# Flight_Computer.net
KiCad netlist of a schematic drawn in EAGLE
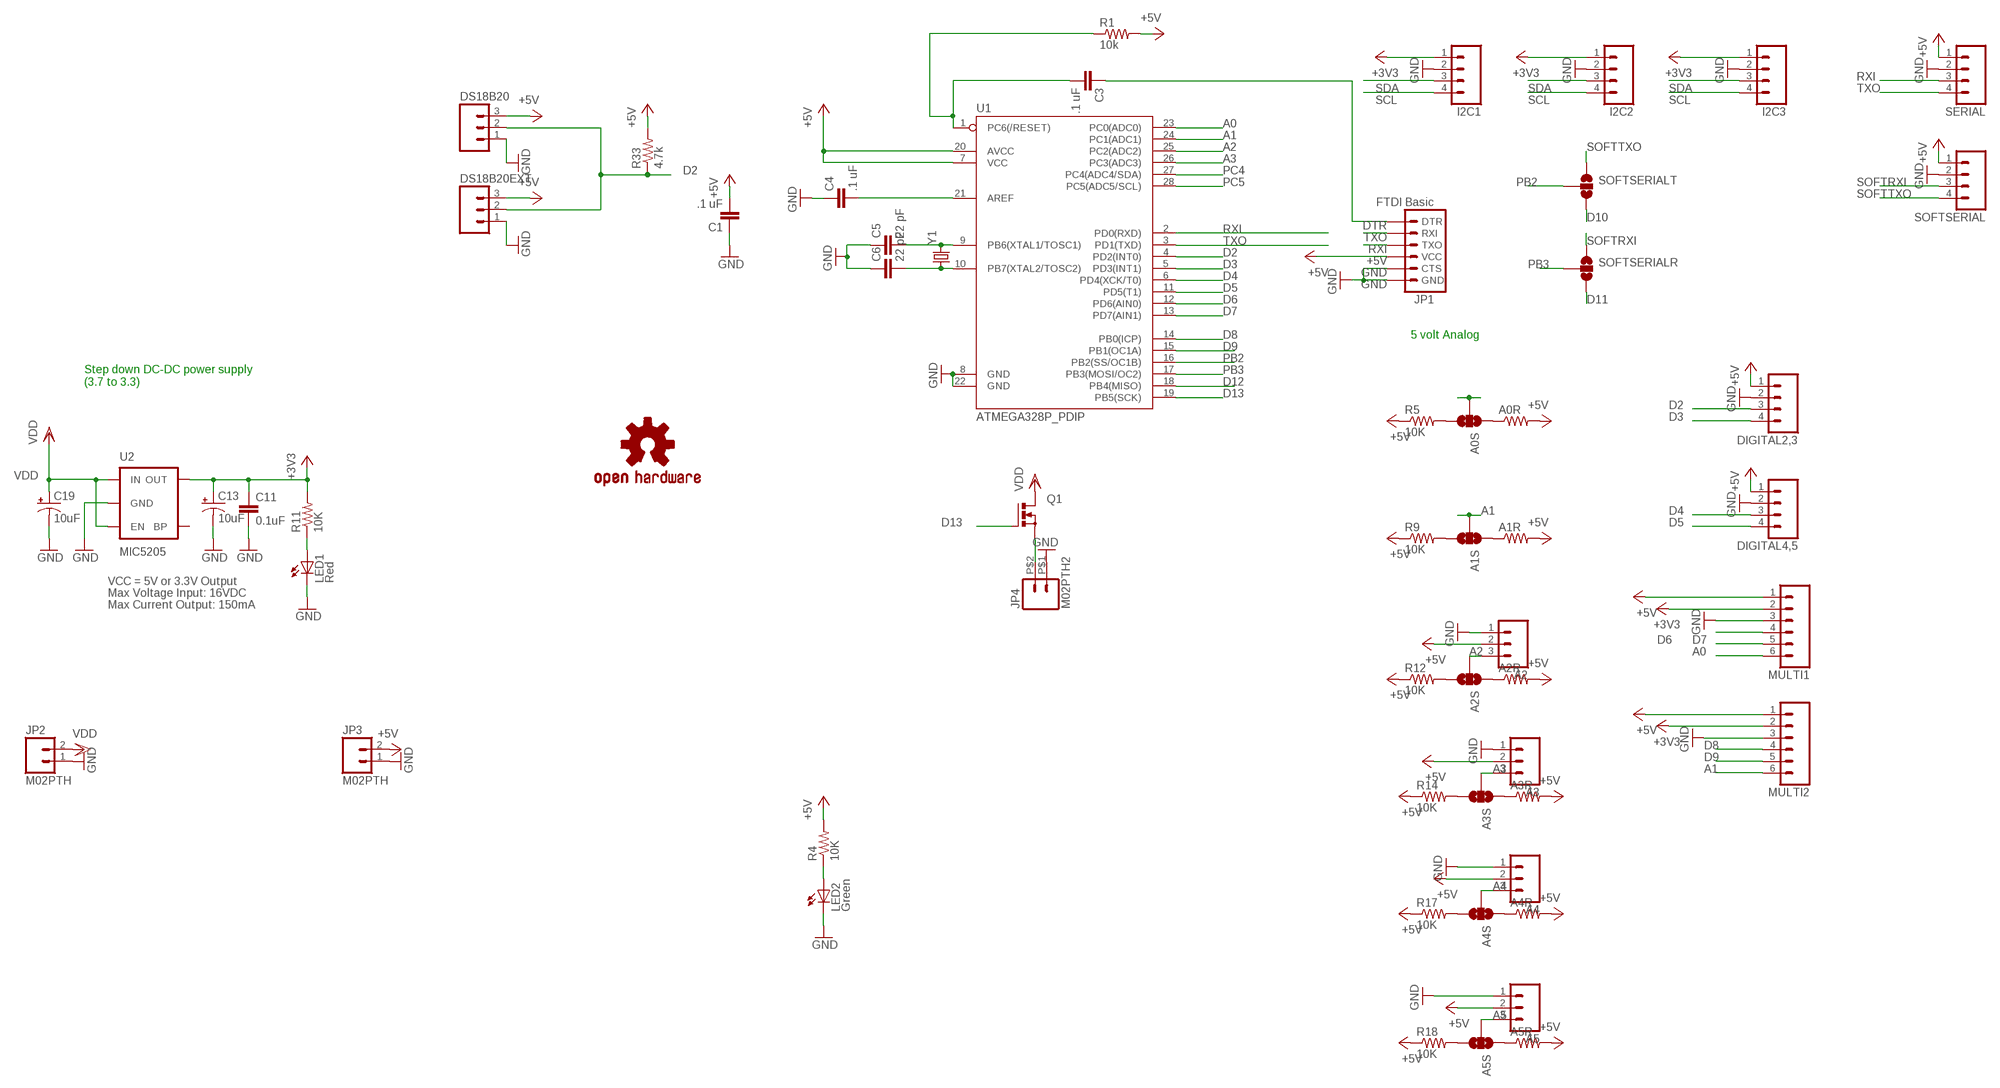
[diagram p0: schematic, sheet 1]

(export (version "E")
  (design (tool "Eeschema 10.0.6"))
  (components
    (comp (ref "A0R")
      (value "RESISTORAXIAL-0.3")
      (footprint "eagle-import:AXIAL-0.3")
      (libsource (lib "eagle-import") (part "SparkFun-Passives_RESISTORAXIAL-0.3"))
    )
    (comp (ref "A0S")
      (value "SOLDERJUMPER_2WAYPASTE2&3")
      (footprint "eagle-import:SJ_3_PASTE2&3")
      (libsource (lib "eagle-import") (part "SOLDERJUMPER_2WAYPASTE2&3"))
    )
    (comp (ref "A1R")
      (value "RESISTORAXIAL-0.3")
      (footprint "eagle-import:AXIAL-0.3")
      (libsource (lib "eagle-import") (part "SparkFun-Passives_RESISTORAXIAL-0.3"))
    )
    (comp (ref "A1S")
      (value "SOLDERJUMPER_2WAYPASTE2&3")
      (footprint "eagle-import:SJ_3_PASTE2&3")
      (libsource (lib "eagle-import") (part "SOLDERJUMPER_2WAYPASTE2&3"))
    )
    (comp (ref "A2")
      (value "M03POLAR")
      (footprint "eagle-import:MOLEX-1X3")
      (libsource (lib "eagle-import") (part "M03POLAR"))
    )
    (comp (ref "A2R")
      (value "RESISTORAXIAL-0.3")
      (footprint "eagle-import:AXIAL-0.3")
      (libsource (lib "eagle-import") (part "SparkFun-Passives_RESISTORAXIAL-0.3"))
    )
    (comp (ref "A2S")
      (value "SOLDERJUMPER_2WAYPASTE2&3")
      (footprint "eagle-import:SJ_3_PASTE2&3")
      (libsource (lib "eagle-import") (part "SOLDERJUMPER_2WAYPASTE2&3"))
    )
    (comp (ref "A3")
      (value "M03POLAR")
      (footprint "eagle-import:MOLEX-1X3")
      (libsource (lib "eagle-import") (part "M03POLAR"))
    )
    (comp (ref "A3R")
      (value "RESISTORAXIAL-0.3")
      (footprint "eagle-import:AXIAL-0.3")
      (libsource (lib "eagle-import") (part "SparkFun-Passives_RESISTORAXIAL-0.3"))
    )
    (comp (ref "A3S")
      (value "SOLDERJUMPER_2WAYPASTE2&3")
      (footprint "eagle-import:SJ_3_PASTE2&3")
      (libsource (lib "eagle-import") (part "SOLDERJUMPER_2WAYPASTE2&3"))
    )
    (comp (ref "A4")
      (value "M03POLAR")
      (footprint "eagle-import:MOLEX-1X3")
      (libsource (lib "eagle-import") (part "M03POLAR"))
    )
    (comp (ref "A4R")
      (value "RESISTORAXIAL-0.3")
      (footprint "eagle-import:AXIAL-0.3")
      (libsource (lib "eagle-import") (part "SparkFun-Passives_RESISTORAXIAL-0.3"))
    )
    (comp (ref "A4S")
      (value "SOLDERJUMPER_2WAYPASTE2&3")
      (footprint "eagle-import:SJ_3_PASTE2&3")
      (libsource (lib "eagle-import") (part "SOLDERJUMPER_2WAYPASTE2&3"))
    )
    (comp (ref "A5")
      (value "M03POLAR")
      (footprint "eagle-import:MOLEX-1X3")
      (libsource (lib "eagle-import") (part "M03POLAR"))
    )
    (comp (ref "A5R")
      (value "RESISTORAXIAL-0.3")
      (footprint "eagle-import:AXIAL-0.3")
      (libsource (lib "eagle-import") (part "SparkFun-Passives_RESISTORAXIAL-0.3"))
    )
    (comp (ref "A5S")
      (value "SOLDERJUMPER_2WAYPASTE2&3")
      (footprint "eagle-import:SJ_3_PASTE2&3")
      (libsource (lib "eagle-import") (part "SOLDERJUMPER_2WAYPASTE2&3"))
    )
    (comp (ref "C1")
      (value ".1 uF")
      (footprint "eagle-import:1206")
      (libsource (lib "eagle-import") (part "SparkFun-Passives_CAP1206"))
    )
    (comp (ref "C3")
      (value ".1 uF")
      (footprint "eagle-import:1206")
      (libsource (lib "eagle-import") (part "SparkFun-Passives_CAP1206"))
    )
    (comp (ref "C4")
      (value ".1 uF")
      (footprint "eagle-import:1206")
      (libsource (lib "eagle-import") (part "SparkFun-Passives_CAP1206"))
    )
    (comp (ref "C5")
      (value "22 pF")
      (footprint "eagle-import:CAP-PTH-5MM")
      (libsource (lib "eagle-import") (part "SparkFun-Passives_CAPPTH1"))
    )
    (comp (ref "C6")
      (value "22 pF")
      (footprint "eagle-import:CAP-PTH-5MM")
      (libsource (lib "eagle-import") (part "SparkFun-Passives_CAPPTH1"))
    )
    (comp (ref "C11")
      (value "0.1uF")
      (footprint "eagle-import:1206")
      (libsource (lib "eagle-import") (part "CAP1206"))
    )
    (comp (ref "C13")
      (value "10uF")
      (footprint "eagle-import:EIA3216")
      (libsource (lib "eagle-import") (part "CAP_POL1206"))
    )
    (comp (ref "C19")
      (value "10uF")
      (footprint "eagle-import:EIA3216")
      (libsource (lib "eagle-import") (part "CAP_POL1206"))
    )
    (comp (ref "DIGITAL2,3")
      (value "M04POLAR")
      (footprint "eagle-import:MOLEX-1X4")
      (libsource (lib "eagle-import") (part "M04POLAR"))
    )
    (comp (ref "DIGITAL4,5")
      (value "M04POLAR")
      (footprint "eagle-import:MOLEX-1X4")
      (libsource (lib "eagle-import") (part "M04POLAR"))
    )
    (comp (ref "DS18B20")
      (value "M03PTH")
      (footprint "eagle-import:1X03")
      (libsource (lib "eagle-import") (part "M03PTH"))
    )
    (comp (ref "DS18B20EXT")
      (value "M03POLAR")
      (footprint "eagle-import:MOLEX-1X3")
      (libsource (lib "eagle-import") (part "M03POLAR"))
    )
    (comp (ref "I2C1")
      (value "M04POLAR")
      (footprint "eagle-import:MOLEX-1X4")
      (libsource (lib "eagle-import") (part "M04POLAR"))
    )
    (comp (ref "I2C2")
      (value "M04POLAR")
      (footprint "eagle-import:MOLEX-1X4")
      (libsource (lib "eagle-import") (part "M04POLAR"))
    )
    (comp (ref "I2C3")
      (value "M04POLAR")
      (footprint "eagle-import:MOLEX-1X4")
      (libsource (lib "eagle-import") (part "M04POLAR"))
    )
    (comp (ref "JP1")
      (value "FTDI Basic")
      (footprint "eagle-import:1X06")
      (libsource (lib "eagle-import") (part "ARDUINO_SERIAL_PROGRAMPTH"))
    )
    (comp (ref "JP2")
      (value "M02PTH")
      (footprint "eagle-import:1X02")
      (libsource (lib "eagle-import") (part "M02PTH"))
    )
    (comp (ref "JP3")
      (value "M02PTH")
      (footprint "eagle-import:1X02")
      (libsource (lib "eagle-import") (part "M02PTH"))
    )
    (comp (ref "JP4")
      (value "M02PTH2")
      (footprint "eagle-import:1X02_BIG")
      (libsource (lib "eagle-import") (part "M02PTH2"))
    )
    (comp (ref "LED1")
      (value "Red")
      (footprint "eagle-import:LED-0603")
      (libsource (lib "eagle-import") (part "LED0603"))
    )
    (comp (ref "LED2")
      (value "Green")
      (footprint "eagle-import:LED-0603")
      (libsource (lib "eagle-import") (part "LED0603"))
    )
    (comp (ref "LOGO1")
      (value "OSHW-LOGOL")
      (footprint "eagle-import:OSHW-LOGO-L")
      (libsource (lib "eagle-import") (part "OSHW-LOGOL"))
    )
    (comp (ref "MULTI1")
      (value "M06POLAR")
      (footprint "eagle-import:MOLEX-1X6")
      (libsource (lib "eagle-import") (part "M06POLAR"))
    )
    (comp (ref "MULTI2")
      (value "M06POLAR")
      (footprint "eagle-import:MOLEX-1X6")
      (libsource (lib "eagle-import") (part "M06POLAR"))
    )
    (comp (ref "Q1")
      (value "PMOSFET_NTO220BV")
      (footprint "eagle-import:TO220BV")
      (libsource (lib "eagle-import") (part "PMOSFET_NTO220BV"))
    )
    (comp (ref "R1")
      (value "10k")
      (footprint "eagle-import:1206")
      (libsource (lib "eagle-import") (part "SparkFun-Passives_RESISTOR1206"))
    )
    (comp (ref "R4")
      (value "10K")
      (footprint "eagle-import:1206")
      (libsource (lib "eagle-import") (part "RESISTOR1206"))
    )
    (comp (ref "R5")
      (value "10K")
      (footprint "eagle-import:1206")
      (libsource (lib "eagle-import") (part "SparkFun-Passives_RESISTOR1206"))
    )
    (comp (ref "R9")
      (value "10K")
      (footprint "eagle-import:1206")
      (libsource (lib "eagle-import") (part "SparkFun-Passives_RESISTOR1206"))
    )
    (comp (ref "R11")
      (value "10K")
      (footprint "eagle-import:1206")
      (libsource (lib "eagle-import") (part "RESISTOR1206"))
    )
    (comp (ref "R12")
      (value "10K")
      (footprint "eagle-import:1206")
      (libsource (lib "eagle-import") (part "SparkFun-Passives_RESISTOR1206"))
    )
    (comp (ref "R14")
      (value "10K")
      (footprint "eagle-import:1206")
      (libsource (lib "eagle-import") (part "SparkFun-Passives_RESISTOR1206"))
    )
    (comp (ref "R17")
      (value "10K")
      (footprint "eagle-import:1206")
      (libsource (lib "eagle-import") (part "SparkFun-Passives_RESISTOR1206"))
    )
    (comp (ref "R18")
      (value "10K")
      (footprint "eagle-import:1206")
      (libsource (lib "eagle-import") (part "SparkFun-Passives_RESISTOR1206"))
    )
    (comp (ref "R33")
      (value "4.7k")
      (footprint "eagle-import:1206")
      (libsource (lib "eagle-import") (part "SparkFun-Passives_RESISTOR1206"))
    )
    (comp (ref "SERIAL")
      (value "M04POLAR")
      (footprint "eagle-import:MOLEX-1X4")
      (libsource (lib "eagle-import") (part "M04POLAR"))
    )
    (comp (ref "SOFTSERIAL")
      (value "M04POLAR")
      (footprint "eagle-import:MOLEX-1X4")
      (libsource (lib "eagle-import") (part "M04POLAR"))
    )
    (comp (ref "SOFTSERIALR")
      (value "SOLDERJUMPER_2WAYPASTE2&3")
      (footprint "eagle-import:SJ_3_PASTE2&3")
      (libsource (lib "eagle-import") (part "SOLDERJUMPER_2WAYPASTE2&3"))
    )
    (comp (ref "SOFTSERIALT")
      (value "SOLDERJUMPER_2WAYPASTE2&3")
      (footprint "eagle-import:SJ_3_PASTE2&3")
      (libsource (lib "eagle-import") (part "SOLDERJUMPER_2WAYPASTE2&3"))
    )
    (comp (ref "U1")
      (value "ATMEGA328P_PDIP")
      (footprint "eagle-import:DIL28-3")
      (libsource (lib "eagle-import") (part "ATMEGA328P_PDIP"))
    )
    (comp (ref "U2")
      (value "MIC5205")
      (footprint "eagle-import:SOT23-5")
      (libsource (lib "eagle-import") (part "V_REG_LDOSMD"))
    )
    (comp (ref "Y1")
      (value "CRYSTALHC49UV")
      (footprint "eagle-import:HC49U-V")
      (libsource (lib "eagle-import") (part "CRYSTALHC49UV"))
    )
  )
  (nets
    (net (code "1") (name "+3V3") (class "Default")
      (node (ref "C11") (pin "1") (pinfunction "1_1") (pintype "passive"))
      (node (ref "C13") (pin "A") (pinfunction "+_A") (pintype "passive"))
      (node (ref "I2C1") (pin "1") (pinfunction "1_1") (pintype "passive"))
      (node (ref "I2C2") (pin "1") (pinfunction "1_1") (pintype "passive"))
      (node (ref "I2C3") (pin "1") (pinfunction "1_1") (pintype "passive"))
      (node (ref "MULTI1") (pin "2") (pinfunction "2_2") (pintype "passive"))
      (node (ref "MULTI2") (pin "2") (pinfunction "2_2") (pintype "passive"))
      (node (ref "R11") (pin "2") (pinfunction "2_2") (pintype "passive"))
      (node (ref "U2") (pin "5") (pinfunction "OUT_5") (pintype "passive"))
    )
    (net (code "2") (name "+5V") (class "Default")
      (node (ref "A0R") (pin "P$2") (pinfunction "2_P$2") (pintype "passive"))
      (node (ref "A1R") (pin "P$2") (pinfunction "2_P$2") (pintype "passive"))
      (node (ref "A2") (pin "2") (pinfunction "2_2") (pintype "passive"))
      (node (ref "A2R") (pin "P$2") (pinfunction "2_P$2") (pintype "passive"))
      (node (ref "A3") (pin "2") (pinfunction "2_2") (pintype "passive"))
      (node (ref "A3R") (pin "P$2") (pinfunction "2_P$2") (pintype "passive"))
      (node (ref "A4") (pin "2") (pinfunction "2_2") (pintype "passive"))
      (node (ref "A4R") (pin "P$2") (pinfunction "2_P$2") (pintype "passive"))
      (node (ref "A5") (pin "2") (pinfunction "2_2") (pintype "passive"))
      (node (ref "A5R") (pin "P$2") (pinfunction "2_P$2") (pintype "passive"))
      (node (ref "C1") (pin "2") (pinfunction "2_2") (pintype "passive"))
      (node (ref "DIGITAL2,3") (pin "1") (pinfunction "1_1") (pintype "passive"))
      (node (ref "DIGITAL4,5") (pin "1") (pinfunction "1_1") (pintype "passive"))
      (node (ref "DS18B20") (pin "3") (pinfunction "3_3") (pintype "passive"))
      (node (ref "DS18B20EXT") (pin "3") (pinfunction "3_3") (pintype "passive"))
      (node (ref "JP1") (pin "4") (pinfunction "VCC_4") (pintype "passive"))
      (node (ref "JP3") (pin "2") (pinfunction "2_2") (pintype "passive"))
      (node (ref "MULTI1") (pin "1") (pinfunction "1_1") (pintype "passive"))
      (node (ref "MULTI2") (pin "1") (pinfunction "1_1") (pintype "passive"))
      (node (ref "R1") (pin "2") (pinfunction "2_2") (pintype "passive"))
      (node (ref "R12") (pin "1") (pinfunction "1_1") (pintype "passive"))
      (node (ref "R14") (pin "1") (pinfunction "1_1") (pintype "passive"))
      (node (ref "R17") (pin "1") (pinfunction "1_1") (pintype "passive"))
      (node (ref "R18") (pin "1") (pinfunction "1_1") (pintype "passive"))
      (node (ref "R33") (pin "2") (pinfunction "2_2") (pintype "passive"))
      (node (ref "R4") (pin "2") (pinfunction "2_2") (pintype "passive"))
      (node (ref "R5") (pin "1") (pinfunction "1_1") (pintype "passive"))
      (node (ref "R9") (pin "1") (pinfunction "1_1") (pintype "passive"))
      (node (ref "SERIAL") (pin "1") (pinfunction "1_1") (pintype "passive"))
      (node (ref "SOFTSERIAL") (pin "1") (pinfunction "1_1") (pintype "passive"))
      (node (ref "U1") (pin "20") (pinfunction "AVCC_20") (pintype "bidirectional"))
      (node (ref "U1") (pin "7") (pinfunction "VCC_7") (pintype "bidirectional"))
    )
    (net (code "3") (name "/A0") (class "Default")
      (node (ref "A0S") (pin "2") (pinfunction "2_2") (pintype "passive"))
      (node (ref "MULTI1") (pin "6") (pinfunction "6_6") (pintype "passive"))
      (node (ref "U1") (pin "23") (pinfunction "PC0(ADC0)_23") (pintype "bidirectional"))
    )
    (net (code "4") (name "/A1") (class "Default")
      (node (ref "A1S") (pin "2") (pinfunction "2_2") (pintype "passive"))
      (node (ref "MULTI2") (pin "6") (pinfunction "6_6") (pintype "passive"))
      (node (ref "U1") (pin "24") (pinfunction "PC1(ADC1)_24") (pintype "bidirectional"))
    )
    (net (code "5") (name "/A2") (class "Default")
      (node (ref "A2") (pin "3") (pinfunction "3_3") (pintype "passive"))
      (node (ref "A2S") (pin "2") (pinfunction "2_2") (pintype "passive"))
      (node (ref "U1") (pin "25") (pinfunction "PC2(ADC2)_25") (pintype "bidirectional"))
    )
    (net (code "6") (name "/A3") (class "Default")
      (node (ref "A3") (pin "3") (pinfunction "3_3") (pintype "passive"))
      (node (ref "A3S") (pin "2") (pinfunction "2_2") (pintype "passive"))
      (node (ref "U1") (pin "26") (pinfunction "PC3(ADC3)_26") (pintype "bidirectional"))
    )
    (net (code "7") (name "/A4") (class "Default")
      (node (ref "A4") (pin "3") (pinfunction "3_3") (pintype "passive"))
      (node (ref "A4S") (pin "2") (pinfunction "2_2") (pintype "passive"))
    )
    (net (code "8") (name "/A5") (class "Default")
      (node (ref "A5") (pin "3") (pinfunction "3_3") (pintype "passive"))
      (node (ref "A5S") (pin "2") (pinfunction "2_2") (pintype "passive"))
    )
    (net (code "9") (name "/D2") (class "Default")
      (node (ref "DIGITAL2,3") (pin "3") (pinfunction "3_3") (pintype "passive"))
      (node (ref "DS18B20") (pin "2") (pinfunction "2_2") (pintype "passive"))
      (node (ref "DS18B20EXT") (pin "2") (pinfunction "2_2") (pintype "passive"))
      (node (ref "R33") (pin "1") (pinfunction "1_1") (pintype "passive"))
      (node (ref "U1") (pin "4") (pinfunction "PD2(INT0)_4") (pintype "bidirectional"))
    )
    (net (code "10") (name "/D3") (class "Default")
      (node (ref "DIGITAL2,3") (pin "4") (pinfunction "4_4") (pintype "passive"))
      (node (ref "U1") (pin "5") (pinfunction "PD3(INT1)_5") (pintype "bidirectional"))
    )
    (net (code "11") (name "/D4") (class "Default")
      (node (ref "DIGITAL4,5") (pin "3") (pinfunction "3_3") (pintype "passive"))
      (node (ref "U1") (pin "6") (pinfunction "PD4(XCK/T0)_6") (pintype "bidirectional"))
    )
    (net (code "12") (name "/D5") (class "Default")
      (node (ref "DIGITAL4,5") (pin "4") (pinfunction "4_4") (pintype "passive"))
      (node (ref "U1") (pin "11") (pinfunction "PD5(T1)_11") (pintype "bidirectional"))
    )
    (net (code "13") (name "/D6") (class "Default")
      (node (ref "MULTI1") (pin "4") (pinfunction "4_4") (pintype "passive"))
      (node (ref "U1") (pin "12") (pinfunction "PD6(AIN0)_12") (pintype "bidirectional"))
    )
    (net (code "14") (name "/D7") (class "Default")
      (node (ref "MULTI1") (pin "5") (pinfunction "5_5") (pintype "passive"))
      (node (ref "U1") (pin "13") (pinfunction "PD7(AIN1)_13") (pintype "bidirectional"))
    )
    (net (code "15") (name "/D8") (class "Default")
      (node (ref "MULTI2") (pin "4") (pinfunction "4_4") (pintype "passive"))
      (node (ref "U1") (pin "14") (pinfunction "PB0(ICP)_14") (pintype "bidirectional"))
    )
    (net (code "16") (name "/D9") (class "Default")
      (node (ref "MULTI2") (pin "5") (pinfunction "5_5") (pintype "passive"))
      (node (ref "U1") (pin "15") (pinfunction "PB1(OC1A)_15") (pintype "bidirectional"))
    )
    (net (code "17") (name "/D10") (class "Default")
      (node (ref "SOFTSERIALT") (pin "3") (pinfunction "3_3") (pintype "passive"))
    )
    (net (code "18") (name "/D11") (class "Default")
      (node (ref "SOFTSERIALR") (pin "3") (pinfunction "3_3") (pintype "passive"))
    )
    (net (code "19") (name "/D12") (class "Default")
      (node (ref "U1") (pin "18") (pinfunction "PB4(MISO)_18") (pintype "bidirectional"))
    )
    (net (code "20") (name "/D13") (class "Default")
      (node (ref "Q1") (pin "G") (pinfunction "G_G") (pintype "passive"))
      (node (ref "U1") (pin "19") (pinfunction "PB5(SCK)_19") (pintype "bidirectional"))
    )
    (net (code "21") (name "/DTR") (class "Default")
      (node (ref "C3") (pin "1") (pinfunction "1_1") (pintype "passive"))
      (node (ref "JP1") (pin "1") (pinfunction "DTR_1") (pintype "passive"))
    )
    (net (code "22") (name "/PB2") (class "Default")
      (node (ref "SOFTSERIALT") (pin "2") (pinfunction "2_2") (pintype "passive"))
      (node (ref "U1") (pin "16") (pinfunction "PB2(SS/OC1B)_16") (pintype "bidirectional"))
    )
    (net (code "23") (name "/PB3") (class "Default")
      (node (ref "SOFTSERIALR") (pin "2") (pinfunction "2_2") (pintype "passive"))
      (node (ref "U1") (pin "17") (pinfunction "PB3(MOSI/OC2)_17") (pintype "bidirectional"))
    )
    (net (code "24") (name "/PC4") (class "Default")
      (node (ref "U1") (pin "27") (pinfunction "PC4(ADC4/SDA)_27") (pintype "bidirectional"))
    )
    (net (code "25") (name "/PC5") (class "Default")
      (node (ref "U1") (pin "28") (pinfunction "PC5(ADC5/SCL)_28") (pintype "bidirectional"))
    )
    (net (code "26") (name "/RXI") (class "Default")
      (node (ref "JP1") (pin "3") (pinfunction "TXO_3") (pintype "passive"))
      (node (ref "SERIAL") (pin "3") (pinfunction "3_3") (pintype "passive"))
      (node (ref "U1") (pin "2") (pinfunction "PD0(RXD)_2") (pintype "bidirectional"))
    )
    (net (code "27") (name "/SCL") (class "Default")
      (node (ref "I2C1") (pin "4") (pinfunction "4_4") (pintype "passive"))
      (node (ref "I2C2") (pin "4") (pinfunction "4_4") (pintype "passive"))
      (node (ref "I2C3") (pin "4") (pinfunction "4_4") (pintype "passive"))
    )
    (net (code "28") (name "/SDA") (class "Default")
      (node (ref "I2C1") (pin "3") (pinfunction "3_3") (pintype "passive"))
      (node (ref "I2C2") (pin "3") (pinfunction "3_3") (pintype "passive"))
      (node (ref "I2C3") (pin "3") (pinfunction "3_3") (pintype "passive"))
    )
    (net (code "29") (name "/SOFTRXI") (class "Default")
      (node (ref "SOFTSERIAL") (pin "3") (pinfunction "3_3") (pintype "passive"))
      (node (ref "SOFTSERIALR") (pin "1") (pinfunction "1_1") (pintype "passive"))
    )
    (net (code "30") (name "/SOFTTXO") (class "Default")
      (node (ref "SOFTSERIAL") (pin "4") (pinfunction "4_4") (pintype "passive"))
      (node (ref "SOFTSERIALT") (pin "1") (pinfunction "1_1") (pintype "passive"))
    )
    (net (code "31") (name "/TXO") (class "Default")
      (node (ref "JP1") (pin "2") (pinfunction "RXI_2") (pintype "passive"))
      (node (ref "SERIAL") (pin "4") (pinfunction "4_4") (pintype "passive"))
      (node (ref "U1") (pin "3") (pinfunction "PD1(TXD)_3") (pintype "bidirectional"))
    )
    (net (code "32") (name "GND") (class "Default")
      (node (ref "A2") (pin "1") (pinfunction "1_1") (pintype "passive"))
      (node (ref "A3") (pin "1") (pinfunction "1_1") (pintype "passive"))
      (node (ref "A4") (pin "1") (pinfunction "1_1") (pintype "passive"))
      (node (ref "A5") (pin "1") (pinfunction "1_1") (pintype "passive"))
      (node (ref "C1") (pin "1") (pinfunction "1_1") (pintype "passive"))
      (node (ref "C11") (pin "2") (pinfunction "2_2") (pintype "passive"))
      (node (ref "C13") (pin "C") (pinfunction "-_C") (pintype "passive"))
      (node (ref "C19") (pin "C") (pinfunction "-_C") (pintype "passive"))
      (node (ref "C4") (pin "1") (pinfunction "1_1") (pintype "passive"))
      (node (ref "C5") (pin "1") (pinfunction "1_1") (pintype "passive"))
      (node (ref "C6") (pin "1") (pinfunction "1_1") (pintype "passive"))
      (node (ref "DIGITAL2,3") (pin "2") (pinfunction "2_2") (pintype "passive"))
      (node (ref "DIGITAL4,5") (pin "2") (pinfunction "2_2") (pintype "passive"))
      (node (ref "DS18B20") (pin "1") (pinfunction "1_1") (pintype "passive"))
      (node (ref "DS18B20EXT") (pin "1") (pinfunction "1_1") (pintype "passive"))
      (node (ref "I2C1") (pin "2") (pinfunction "2_2") (pintype "passive"))
      (node (ref "I2C2") (pin "2") (pinfunction "2_2") (pintype "passive"))
      (node (ref "I2C3") (pin "2") (pinfunction "2_2") (pintype "passive"))
      (node (ref "JP1") (pin "5") (pinfunction "CTS_5") (pintype "passive"))
      (node (ref "JP1") (pin "6") (pinfunction "GND_6") (pintype "passive"))
      (node (ref "JP2") (pin "1") (pinfunction "1_1") (pintype "passive"))
      (node (ref "JP3") (pin "1") (pinfunction "1_1") (pintype "passive"))
      (node (ref "JP4") (pin "P$1") (pinfunction "1_P$1") (pintype "passive"))
      (node (ref "LED1") (pin "C") (pinfunction "C_C") (pintype "passive"))
      (node (ref "LED2") (pin "C") (pinfunction "C_C") (pintype "passive"))
      (node (ref "MULTI1") (pin "3") (pinfunction "3_3") (pintype "passive"))
      (node (ref "MULTI2") (pin "3") (pinfunction "3_3") (pintype "passive"))
      (node (ref "SERIAL") (pin "2") (pinfunction "2_2") (pintype "passive"))
      (node (ref "SOFTSERIAL") (pin "2") (pinfunction "2_2") (pintype "passive"))
      (node (ref "U1") (pin "22") (pinfunction "GND_22") (pintype "bidirectional"))
      (node (ref "U1") (pin "8") (pinfunction "GND_8") (pintype "bidirectional"))
      (node (ref "U2") (pin "2") (pinfunction "GND_2") (pintype "input"))
    )
    (net (code "33") (name "Net-(A0R-1)") (class "Default")
      (node (ref "A0R") (pin "P$1") (pinfunction "1_P$1") (pintype "passive"))
      (node (ref "A0S") (pin "1") (pinfunction "1_1") (pintype "passive"))
    )
    (net (code "34") (name "Net-(A0S-Pad3)") (class "Default")
      (node (ref "A0S") (pin "3") (pinfunction "3_3") (pintype "passive"))
      (node (ref "R5") (pin "2") (pinfunction "2_2") (pintype "passive"))
    )
    (net (code "35") (name "Net-(A1R-1)") (class "Default")
      (node (ref "A1R") (pin "P$1") (pinfunction "1_P$1") (pintype "passive"))
      (node (ref "A1S") (pin "1") (pinfunction "1_1") (pintype "passive"))
    )
    (net (code "36") (name "Net-(A1S-Pad3)") (class "Default")
      (node (ref "A1S") (pin "3") (pinfunction "3_3") (pintype "passive"))
      (node (ref "R9") (pin "2") (pinfunction "2_2") (pintype "passive"))
    )
    (net (code "37") (name "Net-(A2R-1)") (class "Default")
      (node (ref "A2R") (pin "P$1") (pinfunction "1_P$1") (pintype "passive"))
      (node (ref "A2S") (pin "1") (pinfunction "1_1") (pintype "passive"))
    )
    (net (code "38") (name "Net-(A2S-Pad3)") (class "Default")
      (node (ref "A2S") (pin "3") (pinfunction "3_3") (pintype "passive"))
      (node (ref "R12") (pin "2") (pinfunction "2_2") (pintype "passive"))
    )
    (net (code "39") (name "Net-(A3R-1)") (class "Default")
      (node (ref "A3R") (pin "P$1") (pinfunction "1_P$1") (pintype "passive"))
      (node (ref "A3S") (pin "1") (pinfunction "1_1") (pintype "passive"))
    )
    (net (code "40") (name "Net-(A3S-Pad3)") (class "Default")
      (node (ref "A3S") (pin "3") (pinfunction "3_3") (pintype "passive"))
      (node (ref "R14") (pin "2") (pinfunction "2_2") (pintype "passive"))
    )
    (net (code "41") (name "Net-(A4R-1)") (class "Default")
      (node (ref "A4R") (pin "P$1") (pinfunction "1_P$1") (pintype "passive"))
      (node (ref "A4S") (pin "1") (pinfunction "1_1") (pintype "passive"))
    )
    (net (code "42") (name "Net-(A4S-Pad3)") (class "Default")
      (node (ref "A4S") (pin "3") (pinfunction "3_3") (pintype "passive"))
      (node (ref "R17") (pin "2") (pinfunction "2_2") (pintype "passive"))
    )
    (net (code "43") (name "Net-(A5R-1)") (class "Default")
      (node (ref "A5R") (pin "P$1") (pinfunction "1_P$1") (pintype "passive"))
      (node (ref "A5S") (pin "1") (pinfunction "1_1") (pintype "passive"))
    )
    (net (code "44") (name "Net-(A5S-Pad3)") (class "Default")
      (node (ref "A5S") (pin "3") (pinfunction "3_3") (pintype "passive"))
      (node (ref "R18") (pin "2") (pinfunction "2_2") (pintype "passive"))
    )
    (net (code "45") (name "Net-(JP4-2)") (class "Default")
      (node (ref "JP4") (pin "P$2") (pinfunction "2_P$2") (pintype "passive"))
      (node (ref "Q1") (pin "S") (pinfunction "S_S") (pintype "passive"))
    )
    (net (code "46") (name "Net-(LED1-PadA)") (class "Default")
      (node (ref "LED1") (pin "A") (pinfunction "A_A") (pintype "passive"))
      (node (ref "R11") (pin "1") (pinfunction "1_1") (pintype "passive"))
    )
    (net (code "47") (name "Net-(LED2-PadA)") (class "Default")
      (node (ref "LED2") (pin "A") (pinfunction "A_A") (pintype "passive"))
      (node (ref "R4") (pin "1") (pinfunction "1_1") (pintype "passive"))
    )
    (net (code "48") (name "Net-(U1-AREF)") (class "Default")
      (node (ref "C4") (pin "2") (pinfunction "2_2") (pintype "passive"))
      (node (ref "U1") (pin "21") (pinfunction "AREF_21") (pintype "bidirectional"))
    )
    (net (code "49") (name "Net-(U1-PB6(XTAL1{slash}TOSC1))") (class "Default")
      (node (ref "C5") (pin "2") (pinfunction "2_2") (pintype "passive"))
      (node (ref "U1") (pin "9") (pinfunction "PB6(XTAL1/TOSC1)_9") (pintype "bidirectional"))
      (node (ref "Y1") (pin "2") (pinfunction "2_2") (pintype "passive"))
    )
    (net (code "50") (name "Net-(U1-PB7(XTAL2{slash}TOSC2))") (class "Default")
      (node (ref "C6") (pin "2") (pinfunction "2_2") (pintype "passive"))
      (node (ref "U1") (pin "10") (pinfunction "PB7(XTAL2/TOSC2)_10") (pintype "bidirectional"))
      (node (ref "Y1") (pin "1") (pinfunction "1_1") (pintype "passive"))
    )
    (net (code "51") (name "Net-(U1-PC6({slash}RESET))") (class "Default")
      (node (ref "C3") (pin "2") (pinfunction "2_2") (pintype "passive"))
      (node (ref "R1") (pin "1") (pinfunction "1_1") (pintype "passive"))
      (node (ref "U1") (pin "1") (pinfunction "PC6(/RESET)_1") (pintype "bidirectional"))
    )
    (net (code "52") (name "VDD") (class "Default")
      (node (ref "C19") (pin "A") (pinfunction "+_A") (pintype "passive"))
      (node (ref "JP2") (pin "2") (pinfunction "2_2") (pintype "passive"))
      (node (ref "Q1") (pin "D") (pinfunction "D_D") (pintype "passive"))
      (node (ref "U2") (pin "1") (pinfunction "IN_1") (pintype "input"))
      (node (ref "U2") (pin "3") (pinfunction "EN_3") (pintype "input"))
    )
    (net (code "53") (name "unconnected-(U2-BP-Pad4)") (class "Default")
      (node (ref "U2") (pin "4") (pinfunction "BP_4") (pintype "input"))
    )
  )
)
